# serieAX12.net
KiCad netlist of a schematic drawn in EAGLE
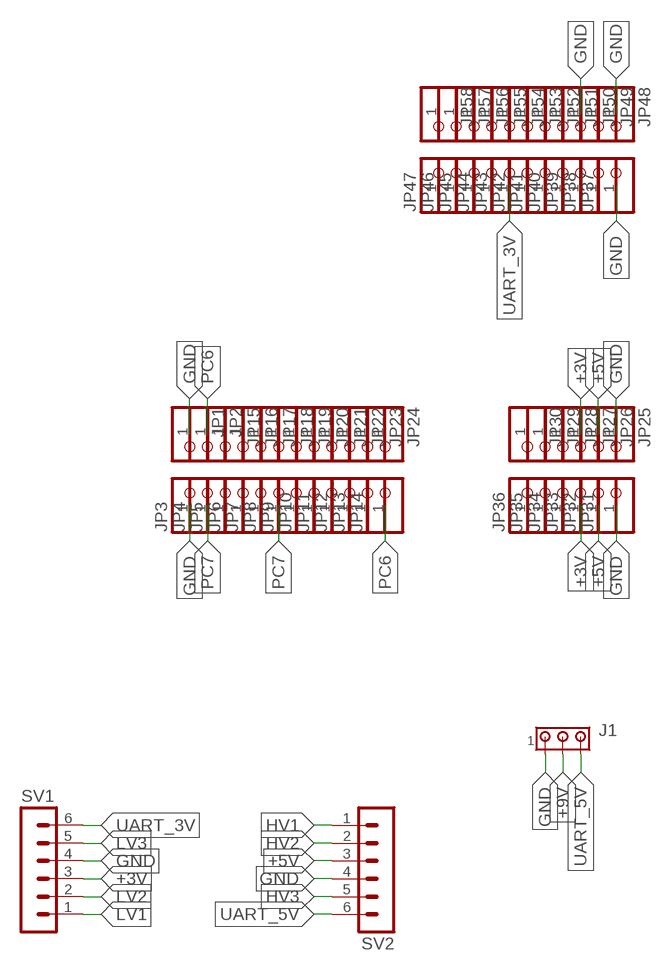
[diagram p0: schematic, sheet 1]

(export (version "E")
  (design (tool "Eeschema 10.0.6"))
  (components
    (comp (ref "J1")
      (value "MTA03-100")
      (footprint "eagle-import:10X03MTA")
      (libsource (lib "eagle-import") (part "MTA03-100"))
    )
    (comp (ref "JP1")
      (value "PINHD-1X1")
      (footprint "eagle-import:1X01")
      (libsource (lib "eagle-import") (part "PINHD-1X1"))
    )
    (comp (ref "JP2")
      (value "PINHD-1X1")
      (footprint "eagle-import:1X01")
      (libsource (lib "eagle-import") (part "PINHD-1X1"))
    )
    (comp (ref "JP3")
      (value "PINHD-1X1")
      (footprint "eagle-import:1X01")
      (libsource (lib "eagle-import") (part "PINHD-1X1"))
    )
    (comp (ref "JP4")
      (value "PINHD-1X1")
      (footprint "eagle-import:1X01")
      (libsource (lib "eagle-import") (part "PINHD-1X1"))
    )
    (comp (ref "JP5")
      (value "PINHD-1X1")
      (footprint "eagle-import:1X01")
      (libsource (lib "eagle-import") (part "PINHD-1X1"))
    )
    (comp (ref "JP6")
      (value "PINHD-1X1")
      (footprint "eagle-import:1X01")
      (libsource (lib "eagle-import") (part "PINHD-1X1"))
    )
    (comp (ref "JP7")
      (value "PINHD-1X1")
      (footprint "eagle-import:1X01")
      (libsource (lib "eagle-import") (part "PINHD-1X1"))
    )
    (comp (ref "JP8")
      (value "PINHD-1X1")
      (footprint "eagle-import:1X01")
      (libsource (lib "eagle-import") (part "PINHD-1X1"))
    )
    (comp (ref "JP9")
      (value "PINHD-1X1")
      (footprint "eagle-import:1X01")
      (libsource (lib "eagle-import") (part "PINHD-1X1"))
    )
    (comp (ref "JP10")
      (value "PINHD-1X1")
      (footprint "eagle-import:1X01")
      (libsource (lib "eagle-import") (part "PINHD-1X1"))
    )
    (comp (ref "JP11")
      (value "PINHD-1X1")
      (footprint "eagle-import:1X01")
      (libsource (lib "eagle-import") (part "PINHD-1X1"))
    )
    (comp (ref "JP12")
      (value "PINHD-1X1")
      (footprint "eagle-import:1X01")
      (libsource (lib "eagle-import") (part "PINHD-1X1"))
    )
    (comp (ref "JP13")
      (value "PINHD-1X1")
      (footprint "eagle-import:1X01")
      (libsource (lib "eagle-import") (part "PINHD-1X1"))
    )
    (comp (ref "JP14")
      (value "PINHD-1X1")
      (footprint "eagle-import:1X01")
      (libsource (lib "eagle-import") (part "PINHD-1X1"))
    )
    (comp (ref "JP15")
      (value "PINHD-1X1")
      (footprint "eagle-import:1X01")
      (libsource (lib "eagle-import") (part "PINHD-1X1"))
    )
    (comp (ref "JP16")
      (value "PINHD-1X1")
      (footprint "eagle-import:1X01")
      (libsource (lib "eagle-import") (part "PINHD-1X1"))
    )
    (comp (ref "JP17")
      (value "PINHD-1X1")
      (footprint "eagle-import:1X01")
      (libsource (lib "eagle-import") (part "PINHD-1X1"))
    )
    (comp (ref "JP18")
      (value "PINHD-1X1")
      (footprint "eagle-import:1X01")
      (libsource (lib "eagle-import") (part "PINHD-1X1"))
    )
    (comp (ref "JP19")
      (value "PINHD-1X1")
      (footprint "eagle-import:1X01")
      (libsource (lib "eagle-import") (part "PINHD-1X1"))
    )
    (comp (ref "JP20")
      (value "PINHD-1X1")
      (footprint "eagle-import:1X01")
      (libsource (lib "eagle-import") (part "PINHD-1X1"))
    )
    (comp (ref "JP21")
      (value "PINHD-1X1")
      (footprint "eagle-import:1X01")
      (libsource (lib "eagle-import") (part "PINHD-1X1"))
    )
    (comp (ref "JP22")
      (value "PINHD-1X1")
      (footprint "eagle-import:1X01")
      (libsource (lib "eagle-import") (part "PINHD-1X1"))
    )
    (comp (ref "JP23")
      (value "PINHD-1X1")
      (footprint "eagle-import:1X01")
      (libsource (lib "eagle-import") (part "PINHD-1X1"))
    )
    (comp (ref "JP24")
      (value "PINHD-1X1")
      (footprint "eagle-import:1X01")
      (libsource (lib "eagle-import") (part "PINHD-1X1"))
    )
    (comp (ref "JP25")
      (value "PINHD-1X1")
      (footprint "eagle-import:1X01")
      (libsource (lib "eagle-import") (part "PINHD-1X1"))
    )
    (comp (ref "JP26")
      (value "PINHD-1X1")
      (footprint "eagle-import:1X01")
      (libsource (lib "eagle-import") (part "PINHD-1X1"))
    )
    (comp (ref "JP27")
      (value "PINHD-1X1")
      (footprint "eagle-import:1X01")
      (libsource (lib "eagle-import") (part "PINHD-1X1"))
    )
    (comp (ref "JP28")
      (value "PINHD-1X1")
      (footprint "eagle-import:1X01")
      (libsource (lib "eagle-import") (part "PINHD-1X1"))
    )
    (comp (ref "JP29")
      (value "PINHD-1X1")
      (footprint "eagle-import:1X01")
      (libsource (lib "eagle-import") (part "PINHD-1X1"))
    )
    (comp (ref "JP30")
      (value "PINHD-1X1")
      (footprint "eagle-import:1X01")
      (libsource (lib "eagle-import") (part "PINHD-1X1"))
    )
    (comp (ref "JP31")
      (value "PINHD-1X1")
      (footprint "eagle-import:1X01")
      (libsource (lib "eagle-import") (part "PINHD-1X1"))
    )
    (comp (ref "JP32")
      (value "PINHD-1X1")
      (footprint "eagle-import:1X01")
      (libsource (lib "eagle-import") (part "PINHD-1X1"))
    )
    (comp (ref "JP33")
      (value "PINHD-1X1")
      (footprint "eagle-import:1X01")
      (libsource (lib "eagle-import") (part "PINHD-1X1"))
    )
    (comp (ref "JP34")
      (value "PINHD-1X1")
      (footprint "eagle-import:1X01")
      (libsource (lib "eagle-import") (part "PINHD-1X1"))
    )
    (comp (ref "JP35")
      (value "PINHD-1X1")
      (footprint "eagle-import:1X01")
      (libsource (lib "eagle-import") (part "PINHD-1X1"))
    )
    (comp (ref "JP36")
      (value "PINHD-1X1")
      (footprint "eagle-import:1X01")
      (libsource (lib "eagle-import") (part "PINHD-1X1"))
    )
    (comp (ref "JP37")
      (value "PINHD-1X1")
      (footprint "eagle-import:1X01")
      (libsource (lib "eagle-import") (part "PINHD-1X1"))
    )
    (comp (ref "JP38")
      (value "PINHD-1X1")
      (footprint "eagle-import:1X01")
      (libsource (lib "eagle-import") (part "PINHD-1X1"))
    )
    (comp (ref "JP39")
      (value "PINHD-1X1")
      (footprint "eagle-import:1X01")
      (libsource (lib "eagle-import") (part "PINHD-1X1"))
    )
    (comp (ref "JP40")
      (value "PINHD-1X1")
      (footprint "eagle-import:1X01")
      (libsource (lib "eagle-import") (part "PINHD-1X1"))
    )
    (comp (ref "JP41")
      (value "PINHD-1X1")
      (footprint "eagle-import:1X01")
      (libsource (lib "eagle-import") (part "PINHD-1X1"))
    )
    (comp (ref "JP42")
      (value "PINHD-1X1")
      (footprint "eagle-import:1X01")
      (libsource (lib "eagle-import") (part "PINHD-1X1"))
    )
    (comp (ref "JP43")
      (value "PINHD-1X1")
      (footprint "eagle-import:1X01")
      (libsource (lib "eagle-import") (part "PINHD-1X1"))
    )
    (comp (ref "JP44")
      (value "PINHD-1X1")
      (footprint "eagle-import:1X01")
      (libsource (lib "eagle-import") (part "PINHD-1X1"))
    )
    (comp (ref "JP45")
      (value "PINHD-1X1")
      (footprint "eagle-import:1X01")
      (libsource (lib "eagle-import") (part "PINHD-1X1"))
    )
    (comp (ref "JP46")
      (value "PINHD-1X1")
      (footprint "eagle-import:1X01")
      (libsource (lib "eagle-import") (part "PINHD-1X1"))
    )
    (comp (ref "JP47")
      (value "PINHD-1X1")
      (footprint "eagle-import:1X01")
      (libsource (lib "eagle-import") (part "PINHD-1X1"))
    )
    (comp (ref "JP48")
      (value "PINHD-1X1")
      (footprint "eagle-import:1X01")
      (libsource (lib "eagle-import") (part "PINHD-1X1"))
    )
    (comp (ref "JP49")
      (value "PINHD-1X1")
      (footprint "eagle-import:1X01")
      (libsource (lib "eagle-import") (part "PINHD-1X1"))
    )
    (comp (ref "JP50")
      (value "PINHD-1X1")
      (footprint "eagle-import:1X01")
      (libsource (lib "eagle-import") (part "PINHD-1X1"))
    )
    (comp (ref "JP51")
      (value "PINHD-1X1")
      (footprint "eagle-import:1X01")
      (libsource (lib "eagle-import") (part "PINHD-1X1"))
    )
    (comp (ref "JP52")
      (value "PINHD-1X1")
      (footprint "eagle-import:1X01")
      (libsource (lib "eagle-import") (part "PINHD-1X1"))
    )
    (comp (ref "JP53")
      (value "PINHD-1X1")
      (footprint "eagle-import:1X01")
      (libsource (lib "eagle-import") (part "PINHD-1X1"))
    )
    (comp (ref "JP54")
      (value "PINHD-1X1")
      (footprint "eagle-import:1X01")
      (libsource (lib "eagle-import") (part "PINHD-1X1"))
    )
    (comp (ref "JP55")
      (value "PINHD-1X1")
      (footprint "eagle-import:1X01")
      (libsource (lib "eagle-import") (part "PINHD-1X1"))
    )
    (comp (ref "JP56")
      (value "PINHD-1X1")
      (footprint "eagle-import:1X01")
      (libsource (lib "eagle-import") (part "PINHD-1X1"))
    )
    (comp (ref "JP57")
      (value "PINHD-1X1")
      (footprint "eagle-import:1X01")
      (libsource (lib "eagle-import") (part "PINHD-1X1"))
    )
    (comp (ref "JP58")
      (value "PINHD-1X1")
      (footprint "eagle-import:1X01")
      (libsource (lib "eagle-import") (part "PINHD-1X1"))
    )
    (comp (ref "SV1")
      (value "MA06-1")
      (footprint "eagle-import:MA06-1")
      (libsource (lib "eagle-import") (part "MA06-1"))
    )
    (comp (ref "SV2")
      (value "MA06-1")
      (footprint "eagle-import:MA06-1")
      (libsource (lib "eagle-import") (part "MA06-1"))
    )
  )
  (nets
    (net (code "1") (name "+3V") (class "Default")
      (node (ref "JP27") (pin "1") (pinfunction "1_1") (pintype "passive"))
      (node (ref "JP33") (pin "1") (pinfunction "1_1") (pintype "passive"))
      (node (ref "SV1") (pin "3") (pinfunction "3_3") (pintype "passive"))
    )
    (net (code "2") (name "+5V") (class "Default")
      (node (ref "JP26") (pin "1") (pinfunction "1_1") (pintype "passive"))
      (node (ref "JP32") (pin "1") (pinfunction "1_1") (pintype "passive"))
      (node (ref "SV2") (pin "3") (pinfunction "3_3") (pintype "passive"))
    )
    (net (code "3") (name "+9V") (class "Default")
      (node (ref "J1") (pin "2") (pinfunction "2_2") (pintype "passive"))
    )
    (net (code "4") (name "GND") (class "Default")
      (node (ref "J1") (pin "1") (pinfunction "1_1") (pintype "passive"))
      (node (ref "JP1") (pin "1") (pinfunction "1_1") (pintype "passive"))
      (node (ref "JP25") (pin "1") (pinfunction "1_1") (pintype "passive"))
      (node (ref "JP3") (pin "1") (pinfunction "1_1") (pintype "passive"))
      (node (ref "JP31") (pin "1") (pinfunction "1_1") (pintype "passive"))
      (node (ref "JP37") (pin "1") (pinfunction "1_1") (pintype "passive"))
      (node (ref "JP48") (pin "1") (pinfunction "1_1") (pintype "passive"))
      (node (ref "JP50") (pin "1") (pinfunction "1_1") (pintype "passive"))
      (node (ref "SV1") (pin "4") (pinfunction "4_4") (pintype "passive"))
      (node (ref "SV2") (pin "4") (pinfunction "4_4") (pintype "passive"))
    )
    (net (code "5") (name "HV1") (class "Default")
      (node (ref "SV2") (pin "1") (pinfunction "1_1") (pintype "passive"))
    )
    (net (code "6") (name "HV2") (class "Default")
      (node (ref "SV2") (pin "2") (pinfunction "2_2") (pintype "passive"))
    )
    (net (code "7") (name "HV3") (class "Default")
      (node (ref "SV2") (pin "5") (pinfunction "5_5") (pintype "passive"))
    )
    (net (code "8") (name "LV1") (class "Default")
      (node (ref "SV1") (pin "1") (pinfunction "1_1") (pintype "passive"))
    )
    (net (code "9") (name "LV2") (class "Default")
      (node (ref "SV1") (pin "2") (pinfunction "2_2") (pintype "passive"))
    )
    (net (code "10") (name "LV3") (class "Default")
      (node (ref "SV1") (pin "5") (pinfunction "5_5") (pintype "passive"))
    )
    (net (code "11") (name "PC6") (class "Default")
      (node (ref "JP14") (pin "1") (pinfunction "1_1") (pintype "passive"))
      (node (ref "JP2") (pin "1") (pinfunction "1_1") (pintype "passive"))
    )
    (net (code "12") (name "PC7") (class "Default")
      (node (ref "JP4") (pin "1") (pinfunction "1_1") (pintype "passive"))
      (node (ref "JP8") (pin "1") (pinfunction "1_1") (pintype "passive"))
    )
    (net (code "13") (name "UART_3V") (class "Default")
      (node (ref "JP43") (pin "1") (pinfunction "1_1") (pintype "passive"))
      (node (ref "SV1") (pin "6") (pinfunction "6_6") (pintype "passive"))
    )
    (net (code "14") (name "UART_5V") (class "Default")
      (node (ref "J1") (pin "3") (pinfunction "3_3") (pintype "passive"))
      (node (ref "SV2") (pin "6") (pinfunction "6_6") (pintype "passive"))
    )
    (net (code "15") (name "unconnected-(JP5-Pad1)") (class "Default")
      (node (ref "JP5") (pin "1") (pinfunction "1_1") (pintype "passive"))
    )
    (net (code "16") (name "unconnected-(JP6-Pad1)") (class "Default")
      (node (ref "JP6") (pin "1") (pinfunction "1_1") (pintype "passive"))
    )
    (net (code "17") (name "unconnected-(JP7-Pad1)") (class "Default")
      (node (ref "JP7") (pin "1") (pinfunction "1_1") (pintype "passive"))
    )
    (net (code "18") (name "unconnected-(JP9-Pad1)") (class "Default")
      (node (ref "JP9") (pin "1") (pinfunction "1_1") (pintype "passive"))
    )
    (net (code "19") (name "unconnected-(JP10-Pad1)") (class "Default")
      (node (ref "JP10") (pin "1") (pinfunction "1_1") (pintype "passive"))
    )
    (net (code "20") (name "unconnected-(JP11-Pad1)") (class "Default")
      (node (ref "JP11") (pin "1") (pinfunction "1_1") (pintype "passive"))
    )
    (net (code "21") (name "unconnected-(JP12-Pad1)") (class "Default")
      (node (ref "JP12") (pin "1") (pinfunction "1_1") (pintype "passive"))
    )
    (net (code "22") (name "unconnected-(JP13-Pad1)") (class "Default")
      (node (ref "JP13") (pin "1") (pinfunction "1_1") (pintype "passive"))
    )
    (net (code "23") (name "unconnected-(JP15-Pad1)") (class "Default")
      (node (ref "JP15") (pin "1") (pinfunction "1_1") (pintype "passive"))
    )
    (net (code "24") (name "unconnected-(JP16-Pad1)") (class "Default")
      (node (ref "JP16") (pin "1") (pinfunction "1_1") (pintype "passive"))
    )
    (net (code "25") (name "unconnected-(JP17-Pad1)") (class "Default")
      (node (ref "JP17") (pin "1") (pinfunction "1_1") (pintype "passive"))
    )
    (net (code "26") (name "unconnected-(JP18-Pad1)") (class "Default")
      (node (ref "JP18") (pin "1") (pinfunction "1_1") (pintype "passive"))
    )
    (net (code "27") (name "unconnected-(JP19-Pad1)") (class "Default")
      (node (ref "JP19") (pin "1") (pinfunction "1_1") (pintype "passive"))
    )
    (net (code "28") (name "unconnected-(JP20-Pad1)") (class "Default")
      (node (ref "JP20") (pin "1") (pinfunction "1_1") (pintype "passive"))
    )
    (net (code "29") (name "unconnected-(JP21-Pad1)") (class "Default")
      (node (ref "JP21") (pin "1") (pinfunction "1_1") (pintype "passive"))
    )
    (net (code "30") (name "unconnected-(JP22-Pad1)") (class "Default")
      (node (ref "JP22") (pin "1") (pinfunction "1_1") (pintype "passive"))
    )
    (net (code "31") (name "unconnected-(JP23-Pad1)") (class "Default")
      (node (ref "JP23") (pin "1") (pinfunction "1_1") (pintype "passive"))
    )
    (net (code "32") (name "unconnected-(JP24-Pad1)") (class "Default")
      (node (ref "JP24") (pin "1") (pinfunction "1_1") (pintype "passive"))
    )
    (net (code "33") (name "unconnected-(JP28-Pad1)") (class "Default")
      (node (ref "JP28") (pin "1") (pinfunction "1_1") (pintype "passive"))
    )
    (net (code "34") (name "unconnected-(JP29-Pad1)") (class "Default")
      (node (ref "JP29") (pin "1") (pinfunction "1_1") (pintype "passive"))
    )
    (net (code "35") (name "unconnected-(JP30-Pad1)") (class "Default")
      (node (ref "JP30") (pin "1") (pinfunction "1_1") (pintype "passive"))
    )
    (net (code "36") (name "unconnected-(JP34-Pad1)") (class "Default")
      (node (ref "JP34") (pin "1") (pinfunction "1_1") (pintype "passive"))
    )
    (net (code "37") (name "unconnected-(JP35-Pad1)") (class "Default")
      (node (ref "JP35") (pin "1") (pinfunction "1_1") (pintype "passive"))
    )
    (net (code "38") (name "unconnected-(JP36-Pad1)") (class "Default")
      (node (ref "JP36") (pin "1") (pinfunction "1_1") (pintype "passive"))
    )
    (net (code "39") (name "unconnected-(JP38-Pad1)") (class "Default")
      (node (ref "JP38") (pin "1") (pinfunction "1_1") (pintype "passive"))
    )
    (net (code "40") (name "unconnected-(JP39-Pad1)") (class "Default")
      (node (ref "JP39") (pin "1") (pinfunction "1_1") (pintype "passive"))
    )
    (net (code "41") (name "unconnected-(JP40-Pad1)") (class "Default")
      (node (ref "JP40") (pin "1") (pinfunction "1_1") (pintype "passive"))
    )
    (net (code "42") (name "unconnected-(JP41-Pad1)") (class "Default")
      (node (ref "JP41") (pin "1") (pinfunction "1_1") (pintype "passive"))
    )
    (net (code "43") (name "unconnected-(JP42-Pad1)") (class "Default")
      (node (ref "JP42") (pin "1") (pinfunction "1_1") (pintype "passive"))
    )
    (net (code "44") (name "unconnected-(JP44-Pad1)") (class "Default")
      (node (ref "JP44") (pin "1") (pinfunction "1_1") (pintype "passive"))
    )
    (net (code "45") (name "unconnected-(JP45-Pad1)") (class "Default")
      (node (ref "JP45") (pin "1") (pinfunction "1_1") (pintype "passive"))
    )
    (net (code "46") (name "unconnected-(JP46-Pad1)") (class "Default")
      (node (ref "JP46") (pin "1") (pinfunction "1_1") (pintype "passive"))
    )
    (net (code "47") (name "unconnected-(JP47-Pad1)") (class "Default")
      (node (ref "JP47") (pin "1") (pinfunction "1_1") (pintype "passive"))
    )
    (net (code "48") (name "unconnected-(JP49-Pad1)") (class "Default")
      (node (ref "JP49") (pin "1") (pinfunction "1_1") (pintype "passive"))
    )
    (net (code "49") (name "unconnected-(JP51-Pad1)") (class "Default")
      (node (ref "JP51") (pin "1") (pinfunction "1_1") (pintype "passive"))
    )
    (net (code "50") (name "unconnected-(JP52-Pad1)") (class "Default")
      (node (ref "JP52") (pin "1") (pinfunction "1_1") (pintype "passive"))
    )
    (net (code "51") (name "unconnected-(JP53-Pad1)") (class "Default")
      (node (ref "JP53") (pin "1") (pinfunction "1_1") (pintype "passive"))
    )
    (net (code "52") (name "unconnected-(JP54-Pad1)") (class "Default")
      (node (ref "JP54") (pin "1") (pinfunction "1_1") (pintype "passive"))
    )
    (net (code "53") (name "unconnected-(JP55-Pad1)") (class "Default")
      (node (ref "JP55") (pin "1") (pinfunction "1_1") (pintype "passive"))
    )
    (net (code "54") (name "unconnected-(JP56-Pad1)") (class "Default")
      (node (ref "JP56") (pin "1") (pinfunction "1_1") (pintype "passive"))
    )
    (net (code "55") (name "unconnected-(JP57-Pad1)") (class "Default")
      (node (ref "JP57") (pin "1") (pinfunction "1_1") (pintype "passive"))
    )
    (net (code "56") (name "unconnected-(JP58-Pad1)") (class "Default")
      (node (ref "JP58") (pin "1") (pinfunction "1_1") (pintype "passive"))
    )
  )
)
